# SolarPanelOptimizer.net
KiCad netlist of a schematic drawn in EAGLE
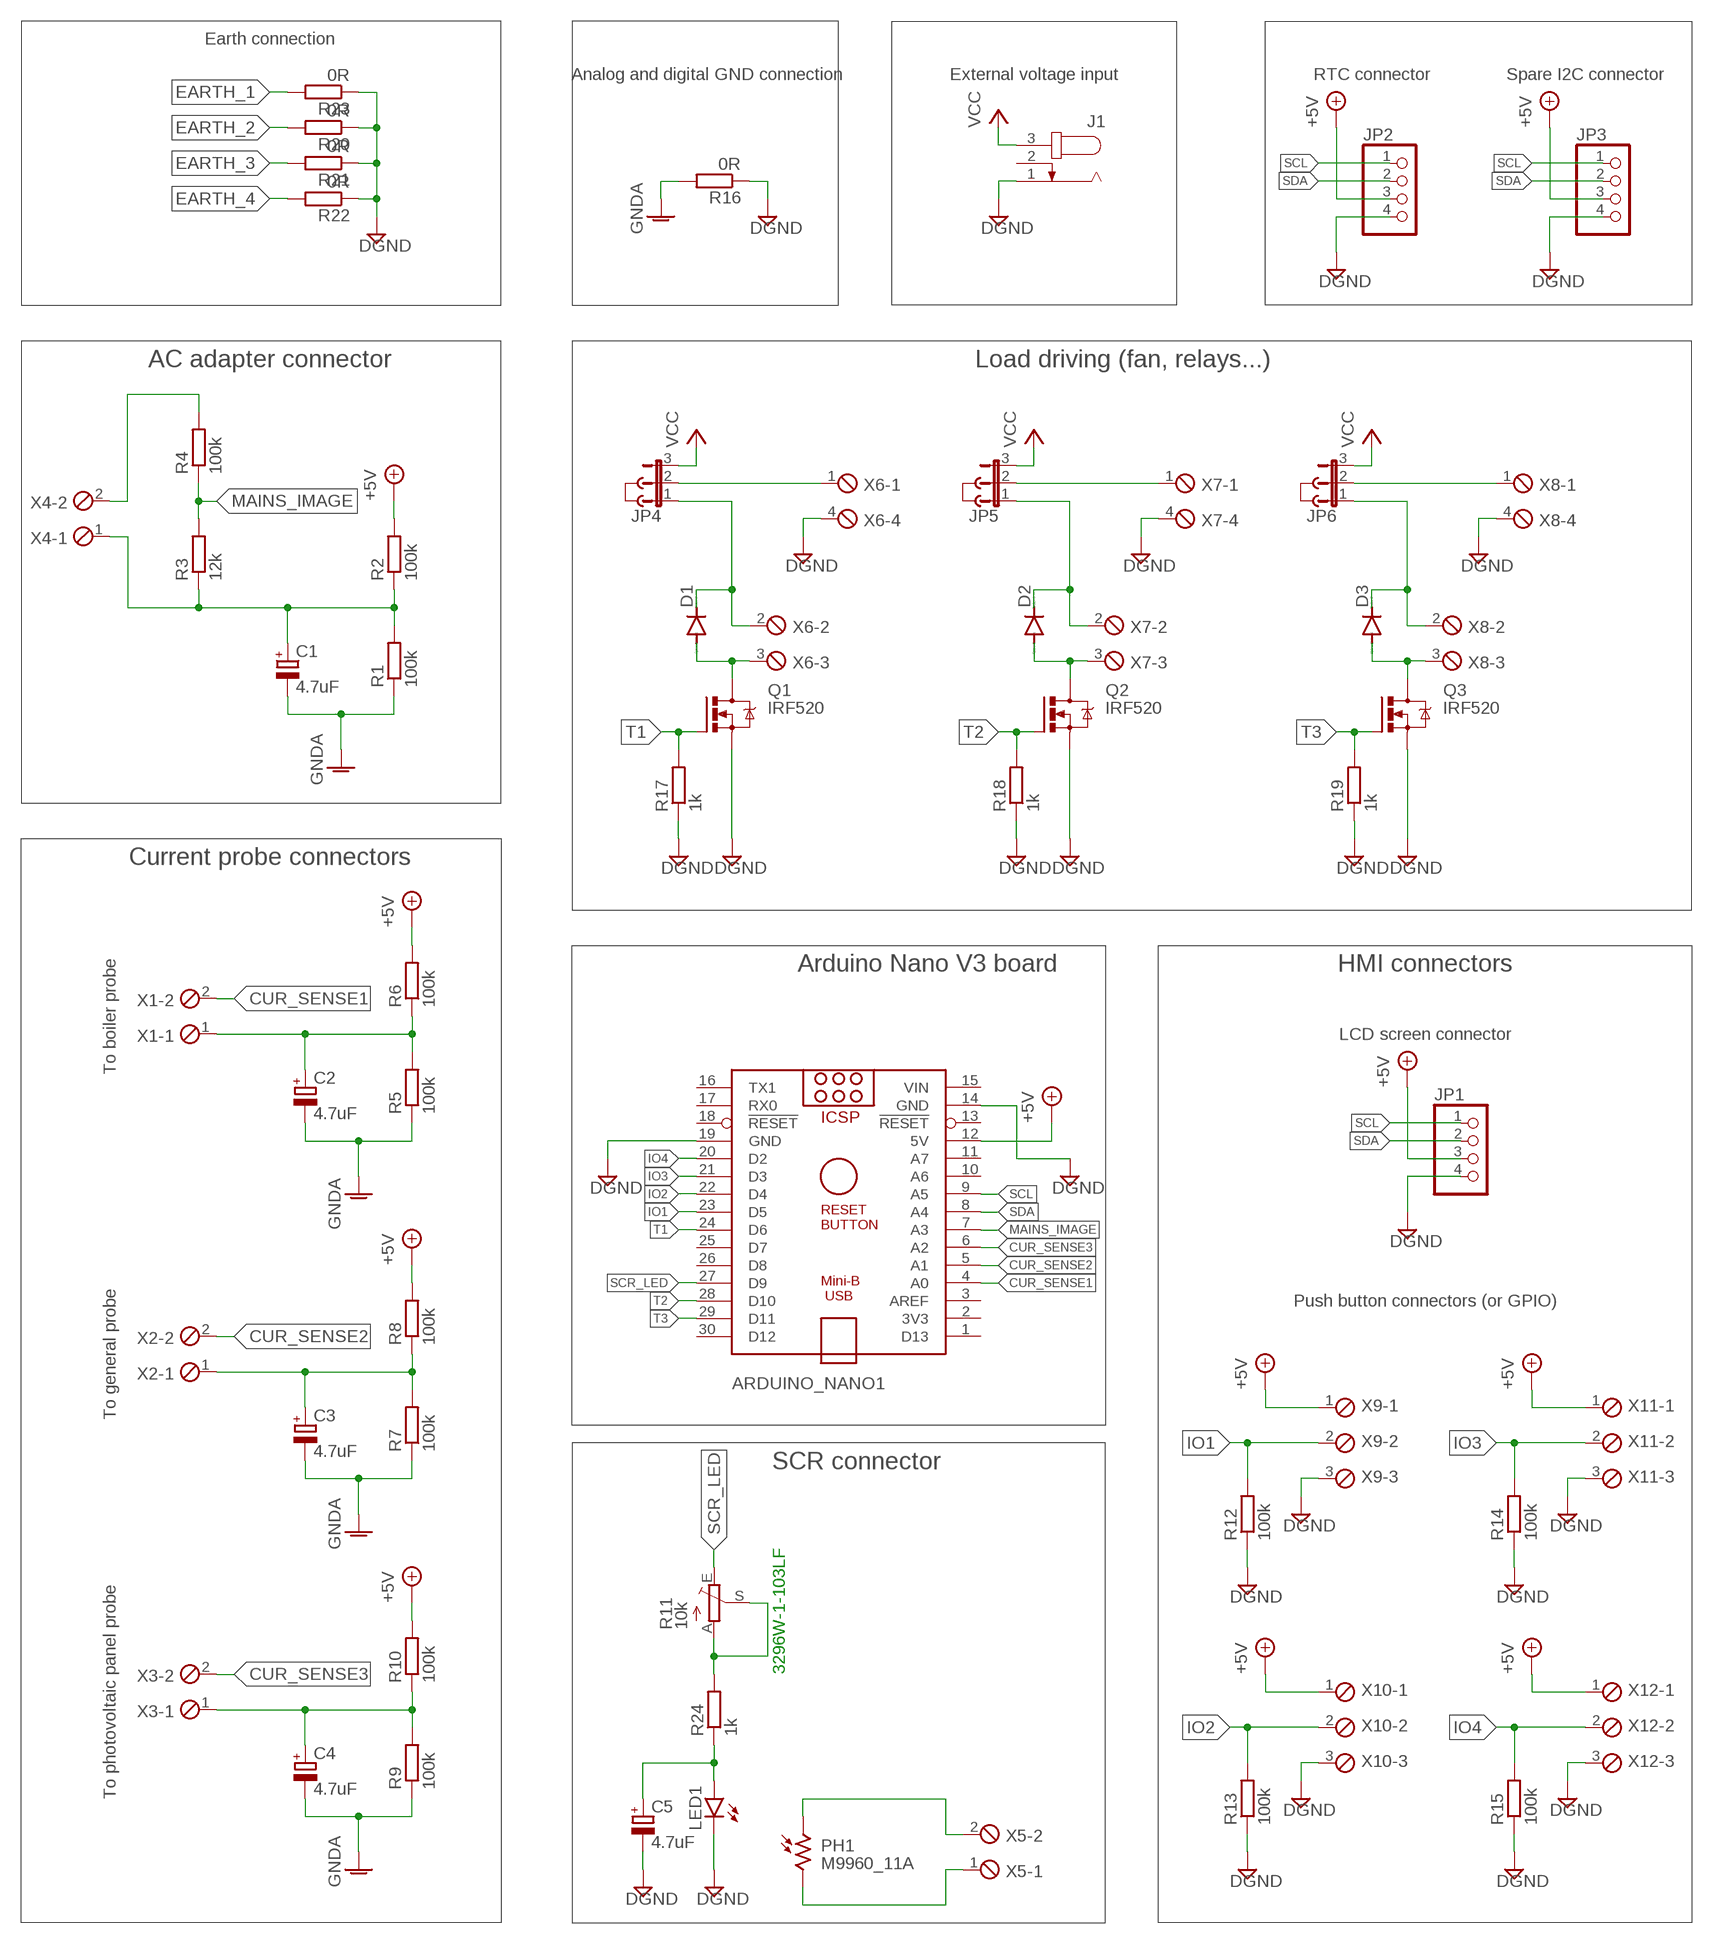
[diagram p0: schematic, sheet 1]

(export (version "E")
  (design (tool "Eeschema 10.0.6"))
  (components
    (comp (ref "ARDUINO_NANO1")
      (value "ARDUINO_NANO")
      (footprint "eagle-import:ARDUINO_NANO")
      (libsource (lib "eagle-import") (part "ARDUINO_NANO"))
    )
    (comp (ref "C1")
      (value "4.7uF")
      (footprint "eagle-import:E2-5")
      (libsource (lib "eagle-import") (part "CPOL-EUE2-5"))
    )
    (comp (ref "C2")
      (value "4.7uF")
      (footprint "eagle-import:E2-5")
      (libsource (lib "eagle-import") (part "CPOL-EUE2-5"))
    )
    (comp (ref "C3")
      (value "4.7uF")
      (footprint "eagle-import:E2-5")
      (libsource (lib "eagle-import") (part "CPOL-EUE2-5"))
    )
    (comp (ref "C4")
      (value "4.7uF")
      (footprint "eagle-import:E2-5")
      (libsource (lib "eagle-import") (part "CPOL-EUE2-5"))
    )
    (comp (ref "C5")
      (value "4.7uF")
      (footprint "eagle-import:E2-5")
      (libsource (lib "eagle-import") (part "CPOL-EUE2-5"))
    )
    (comp (ref "D1")
      (value "DIODE-D-2.5")
      (footprint "eagle-import:D-2.5")
      (libsource (lib "eagle-import") (part "DIODE-D-2.5"))
    )
    (comp (ref "D2")
      (value "DIODE-D-2.5")
      (footprint "eagle-import:D-2.5")
      (libsource (lib "eagle-import") (part "DIODE-D-2.5"))
    )
    (comp (ref "D3")
      (value "DIODE-D-2.5")
      (footprint "eagle-import:D-2.5")
      (libsource (lib "eagle-import") (part "DIODE-D-2.5"))
    )
    (comp (ref "J1")
      (value "JACK-PLUG0")
      (footprint "eagle-import:SPC4077")
      (libsource (lib "eagle-import") (part "JACK-PLUG0"))
    )
    (comp (ref "J2")
      (value "JUMPER")
      (footprint "eagle-import:JUMP")
      (libsource (lib "eagle-import") (part "JUMPER"))
    )
    (comp (ref "J3")
      (value "JUMPER")
      (footprint "eagle-import:JUMP")
      (libsource (lib "eagle-import") (part "JUMPER"))
    )
    (comp (ref "J4")
      (value "JUMPER")
      (footprint "eagle-import:JUMP")
      (libsource (lib "eagle-import") (part "JUMPER"))
    )
    (comp (ref "JP1")
      (value "PINHD-1X4")
      (footprint "eagle-import:1X04")
      (libsource (lib "eagle-import") (part "PINHD-1X4"))
    )
    (comp (ref "JP2")
      (value "PINHD-1X4")
      (footprint "eagle-import:1X04")
      (libsource (lib "eagle-import") (part "PINHD-1X4"))
    )
    (comp (ref "JP3")
      (value "PINHD-1X4")
      (footprint "eagle-import:1X04")
      (libsource (lib "eagle-import") (part "PINHD-1X4"))
    )
    (comp (ref "JP4")
      (value "JP2E")
      (footprint "eagle-import:JP2")
      (libsource (lib "eagle-import") (part "JP2E"))
    )
    (comp (ref "JP5")
      (value "JP2E")
      (footprint "eagle-import:JP2")
      (libsource (lib "eagle-import") (part "JP2E"))
    )
    (comp (ref "JP6")
      (value "JP2E")
      (footprint "eagle-import:JP2")
      (libsource (lib "eagle-import") (part "JP2E"))
    )
    (comp (ref "LED1")
      (value "LED3MM")
      (footprint "eagle-import:LED3MM")
      (libsource (lib "eagle-import") (part "LED3MM"))
    )
    (comp (ref "PH1")
      (value "M9960_11A")
      (footprint "eagle-import:M9960")
      (libsource (lib "eagle-import") (part "M9960_11A"))
    )
    (comp (ref "Q1")
      (value "IRF520")
      (footprint "eagle-import:TO220BV")
      (libsource (lib "eagle-import") (part "IRF520"))
    )
    (comp (ref "Q2")
      (value "IRF520")
      (footprint "eagle-import:TO220BV")
      (libsource (lib "eagle-import") (part "IRF520"))
    )
    (comp (ref "Q3")
      (value "IRF520")
      (footprint "eagle-import:TO220BV")
      (libsource (lib "eagle-import") (part "IRF520"))
    )
    (comp (ref "R1")
      (value "100k")
      (footprint "eagle-import:0204V")
      (libsource (lib "eagle-import") (part "R-EU_0204/2V"))
    )
    (comp (ref "R2")
      (value "100k")
      (footprint "eagle-import:0204V")
      (libsource (lib "eagle-import") (part "R-EU_0204/2V"))
    )
    (comp (ref "R3")
      (value "12k")
      (footprint "eagle-import:0204V")
      (libsource (lib "eagle-import") (part "R-EU_0204/2V"))
    )
    (comp (ref "R4")
      (value "100k")
      (footprint "eagle-import:0204V")
      (libsource (lib "eagle-import") (part "R-EU_0204/2V"))
    )
    (comp (ref "R5")
      (value "100k")
      (footprint "eagle-import:0204V")
      (libsource (lib "eagle-import") (part "R-EU_0204/2V"))
    )
    (comp (ref "R6")
      (value "100k")
      (footprint "eagle-import:0204V")
      (libsource (lib "eagle-import") (part "R-EU_0204/2V"))
    )
    (comp (ref "R7")
      (value "100k")
      (footprint "eagle-import:0204V")
      (libsource (lib "eagle-import") (part "R-EU_0204/2V"))
    )
    (comp (ref "R8")
      (value "100k")
      (footprint "eagle-import:0204V")
      (libsource (lib "eagle-import") (part "R-EU_0204/2V"))
    )
    (comp (ref "R9")
      (value "100k")
      (footprint "eagle-import:0204V")
      (libsource (lib "eagle-import") (part "R-EU_0204/2V"))
    )
    (comp (ref "R10")
      (value "100k")
      (footprint "eagle-import:0204V")
      (libsource (lib "eagle-import") (part "R-EU_0204/2V"))
    )
    (comp (ref "R11")
      (value "10k")
      (footprint "eagle-import:RJ9W")
      (libsource (lib "eagle-import") (part "TRIM_EU-RJ9W"))
    )
    (comp (ref "R12")
      (value "100k")
      (footprint "eagle-import:0204V")
      (libsource (lib "eagle-import") (part "R-EU_0204/2V"))
    )
    (comp (ref "R13")
      (value "100k")
      (footprint "eagle-import:0204V")
      (libsource (lib "eagle-import") (part "R-EU_0204/2V"))
    )
    (comp (ref "R14")
      (value "100k")
      (footprint "eagle-import:0204V")
      (libsource (lib "eagle-import") (part "R-EU_0204/2V"))
    )
    (comp (ref "R15")
      (value "100k")
      (footprint "eagle-import:0204V")
      (libsource (lib "eagle-import") (part "R-EU_0204/2V"))
    )
    (comp (ref "R16")
      (value "0R")
      (footprint "eagle-import:R0805")
      (libsource (lib "eagle-import") (part "R-EU_R0805"))
    )
    (comp (ref "R17")
      (value "1k")
      (footprint "eagle-import:0204V")
      (libsource (lib "eagle-import") (part "R-EU_0204/2V"))
    )
    (comp (ref "R18")
      (value "1k")
      (footprint "eagle-import:0204V")
      (libsource (lib "eagle-import") (part "R-EU_0204/2V"))
    )
    (comp (ref "R19")
      (value "1k")
      (footprint "eagle-import:0204V")
      (libsource (lib "eagle-import") (part "R-EU_0204/2V"))
    )
    (comp (ref "R20")
      (value "0R")
      (footprint "eagle-import:R0805")
      (libsource (lib "eagle-import") (part "R-EU_R0805"))
    )
    (comp (ref "R21")
      (value "0R")
      (footprint "eagle-import:R0805")
      (libsource (lib "eagle-import") (part "R-EU_R0805"))
    )
    (comp (ref "R22")
      (value "0R")
      (footprint "eagle-import:R0805")
      (libsource (lib "eagle-import") (part "R-EU_R0805"))
    )
    (comp (ref "R23")
      (value "0R")
      (footprint "eagle-import:R0805")
      (libsource (lib "eagle-import") (part "R-EU_R0805"))
    )
    (comp (ref "R24")
      (value "1k")
      (footprint "eagle-import:0204V")
      (libsource (lib "eagle-import") (part "R-EU_0204/2V"))
    )
    (comp (ref "X1")
      (value "MPT2-REAL")
      (footprint "eagle-import:2POL254-REAL")
      (libsource (lib "eagle-import") (part "MPT2-REAL"))
    )
    (comp (ref "X2")
      (value "MPT2-REAL")
      (footprint "eagle-import:2POL254-REAL")
      (libsource (lib "eagle-import") (part "MPT2-REAL"))
    )
    (comp (ref "X3")
      (value "MPT2-REAL")
      (footprint "eagle-import:2POL254-REAL")
      (libsource (lib "eagle-import") (part "MPT2-REAL"))
    )
    (comp (ref "X4")
      (value "MPT2-REAL")
      (footprint "eagle-import:2POL254-REAL")
      (libsource (lib "eagle-import") (part "MPT2-REAL"))
    )
    (comp (ref "X5")
      (value "MPT2-REAL")
      (footprint "eagle-import:2POL254-REAL")
      (libsource (lib "eagle-import") (part "MPT2-REAL"))
    )
    (comp (ref "X6")
      (value "MPT4-REAL")
      (footprint "eagle-import:4POL254-REAL")
      (libsource (lib "eagle-import") (part "MPT4-REAL"))
    )
    (comp (ref "X7")
      (value "MPT4-REAL")
      (footprint "eagle-import:4POL254-REAL")
      (libsource (lib "eagle-import") (part "MPT4-REAL"))
    )
    (comp (ref "X8")
      (value "MPT4-REAL")
      (footprint "eagle-import:4POL254-REAL")
      (libsource (lib "eagle-import") (part "MPT4-REAL"))
    )
    (comp (ref "X9")
      (value "MPT3-REAL")
      (footprint "eagle-import:3POL254-REAL")
      (libsource (lib "eagle-import") (part "MPT3-REAL"))
    )
    (comp (ref "X10")
      (value "MPT3-REAL")
      (footprint "eagle-import:3POL254-REAL")
      (libsource (lib "eagle-import") (part "MPT3-REAL"))
    )
    (comp (ref "X11")
      (value "MPT3-REAL")
      (footprint "eagle-import:3POL254-REAL")
      (libsource (lib "eagle-import") (part "MPT3-REAL"))
    )
    (comp (ref "X12")
      (value "MPT3-REAL")
      (footprint "eagle-import:3POL254-REAL")
      (libsource (lib "eagle-import") (part "MPT3-REAL"))
    )
  )
  (nets
    (net (code "1") (name "+5V") (class "Default")
      (node (ref "ARDUINO_NANO1") (pin "12") (pinfunction "5V_12") (pintype "power_in"))
      (node (ref "JP1") (pin "3") (pinfunction "3_3") (pintype "passive"))
      (node (ref "JP2") (pin "3") (pinfunction "3_3") (pintype "passive"))
      (node (ref "JP3") (pin "3") (pinfunction "3_3") (pintype "passive"))
      (node (ref "R10") (pin "2") (pinfunction "2_2") (pintype "passive"))
      (node (ref "R2") (pin "2") (pinfunction "2_2") (pintype "passive"))
      (node (ref "R6") (pin "2") (pinfunction "2_2") (pintype "passive"))
      (node (ref "R8") (pin "2") (pinfunction "2_2") (pintype "passive"))
      (node (ref "X10") (pin "1") (pinfunction "1_1") (pintype "passive"))
      (node (ref "X11") (pin "1") (pinfunction "1_1") (pintype "passive"))
      (node (ref "X12") (pin "1") (pinfunction "1_1") (pintype "passive"))
      (node (ref "X9") (pin "1") (pinfunction "1_1") (pintype "passive"))
    )
    (net (code "2") (name "/VIN") (class "Default")
      (node (ref "ARDUINO_NANO1") (pin "15") (pinfunction "VIN_15") (pintype "power_in"))
    )
    (net (code "3") (name "CUR_SENSE1") (class "Default")
      (node (ref "ARDUINO_NANO1") (pin "4") (pinfunction "A0_4") (pintype "bidirectional"))
      (node (ref "X1") (pin "2") (pinfunction "1_2") (pintype "passive"))
    )
    (net (code "4") (name "CUR_SENSE2") (class "Default")
      (node (ref "ARDUINO_NANO1") (pin "5") (pinfunction "A1_5") (pintype "bidirectional"))
      (node (ref "X2") (pin "2") (pinfunction "1_2") (pintype "passive"))
    )
    (net (code "5") (name "CUR_SENSE3") (class "Default")
      (node (ref "ARDUINO_NANO1") (pin "6") (pinfunction "A2_6") (pintype "bidirectional"))
      (node (ref "X3") (pin "2") (pinfunction "1_2") (pintype "passive"))
    )
    (net (code "6") (name "DGND") (class "Default")
      (node (ref "ARDUINO_NANO1") (pin "14") (pinfunction "GND_14") (pintype "power_in"))
      (node (ref "ARDUINO_NANO1") (pin "19") (pinfunction "GND_19") (pintype "power_in"))
      (node (ref "C5") (pin "-") (pinfunction "-_-") (pintype "passive"))
      (node (ref "J1") (pin "1") (pinfunction "1_1") (pintype "passive"))
      (node (ref "JP1") (pin "4") (pinfunction "4_4") (pintype "passive"))
      (node (ref "JP2") (pin "4") (pinfunction "4_4") (pintype "passive"))
      (node (ref "JP3") (pin "4") (pinfunction "4_4") (pintype "passive"))
      (node (ref "LED1") (pin "K") (pinfunction "C_K") (pintype "passive"))
      (node (ref "Q1") (pin "S") (pinfunction "S_S") (pintype "passive"))
      (node (ref "Q2") (pin "S") (pinfunction "S_S") (pintype "passive"))
      (node (ref "Q3") (pin "S") (pinfunction "S_S") (pintype "passive"))
      (node (ref "R12") (pin "1") (pinfunction "1_1") (pintype "passive"))
      (node (ref "R13") (pin "1") (pinfunction "1_1") (pintype "passive"))
      (node (ref "R14") (pin "1") (pinfunction "1_1") (pintype "passive"))
      (node (ref "R15") (pin "1") (pinfunction "1_1") (pintype "passive"))
      (node (ref "R16") (pin "1") (pinfunction "1_1") (pintype "passive"))
      (node (ref "R17") (pin "1") (pinfunction "1_1") (pintype "passive"))
      (node (ref "R18") (pin "1") (pinfunction "1_1") (pintype "passive"))
      (node (ref "R19") (pin "1") (pinfunction "1_1") (pintype "passive"))
      (node (ref "R20") (pin "1") (pinfunction "1_1") (pintype "passive"))
      (node (ref "R21") (pin "1") (pinfunction "1_1") (pintype "passive"))
      (node (ref "R22") (pin "1") (pinfunction "1_1") (pintype "passive"))
      (node (ref "R23") (pin "1") (pinfunction "1_1") (pintype "passive"))
      (node (ref "X10") (pin "3") (pinfunction "1_3") (pintype "passive"))
      (node (ref "X11") (pin "3") (pinfunction "1_3") (pintype "passive"))
      (node (ref "X12") (pin "3") (pinfunction "1_3") (pintype "passive"))
      (node (ref "X6") (pin "4") (pinfunction "1_4") (pintype "passive"))
      (node (ref "X7") (pin "4") (pinfunction "1_4") (pintype "passive"))
      (node (ref "X8") (pin "4") (pinfunction "1_4") (pintype "passive"))
      (node (ref "X9") (pin "3") (pinfunction "1_3") (pintype "passive"))
    )
    (net (code "7") (name "EARTH_1") (class "Default")
      (node (ref "R23") (pin "2") (pinfunction "2_2") (pintype "passive"))
    )
    (net (code "8") (name "EARTH_2") (class "Default")
      (node (ref "R20") (pin "2") (pinfunction "2_2") (pintype "passive"))
    )
    (net (code "9") (name "EARTH_3") (class "Default")
      (node (ref "R21") (pin "2") (pinfunction "2_2") (pintype "passive"))
    )
    (net (code "10") (name "EARTH_4") (class "Default")
      (node (ref "R22") (pin "2") (pinfunction "2_2") (pintype "passive"))
    )
    (net (code "11") (name "GNDA") (class "Default")
      (node (ref "C1") (pin "-") (pinfunction "-_-") (pintype "passive"))
      (node (ref "C2") (pin "-") (pinfunction "-_-") (pintype "passive"))
      (node (ref "C3") (pin "-") (pinfunction "-_-") (pintype "passive"))
      (node (ref "C4") (pin "-") (pinfunction "-_-") (pintype "passive"))
      (node (ref "R1") (pin "1") (pinfunction "1_1") (pintype "passive"))
      (node (ref "R16") (pin "2") (pinfunction "2_2") (pintype "passive"))
      (node (ref "R5") (pin "1") (pinfunction "1_1") (pintype "passive"))
      (node (ref "R7") (pin "1") (pinfunction "1_1") (pintype "passive"))
      (node (ref "R9") (pin "1") (pinfunction "1_1") (pintype "passive"))
    )
    (net (code "12") (name "IO1") (class "Default")
      (node (ref "ARDUINO_NANO1") (pin "23") (pinfunction "D5_23") (pintype "bidirectional"))
      (node (ref "R12") (pin "2") (pinfunction "2_2") (pintype "passive"))
      (node (ref "X9") (pin "2") (pinfunction "1_2") (pintype "passive"))
    )
    (net (code "13") (name "IO2") (class "Default")
      (node (ref "ARDUINO_NANO1") (pin "22") (pinfunction "D4_22") (pintype "bidirectional"))
      (node (ref "R13") (pin "2") (pinfunction "2_2") (pintype "passive"))
      (node (ref "X10") (pin "2") (pinfunction "1_2") (pintype "passive"))
    )
    (net (code "14") (name "IO3") (class "Default")
      (node (ref "ARDUINO_NANO1") (pin "21") (pinfunction "D3_21") (pintype "bidirectional"))
      (node (ref "R14") (pin "2") (pinfunction "2_2") (pintype "passive"))
      (node (ref "X11") (pin "2") (pinfunction "1_2") (pintype "passive"))
    )
    (net (code "15") (name "IO4") (class "Default")
      (node (ref "ARDUINO_NANO1") (pin "20") (pinfunction "D2_20") (pintype "bidirectional"))
      (node (ref "R15") (pin "2") (pinfunction "2_2") (pintype "passive"))
      (node (ref "X12") (pin "2") (pinfunction "1_2") (pintype "passive"))
    )
    (net (code "16") (name "MAINS_IMAGE") (class "Default")
      (node (ref "ARDUINO_NANO1") (pin "7") (pinfunction "A3_7") (pintype "bidirectional"))
      (node (ref "R3") (pin "2") (pinfunction "2_2") (pintype "passive"))
      (node (ref "R4") (pin "1") (pinfunction "1_1") (pintype "passive"))
    )
    (net (code "17") (name "Net-(C1-Pad+)") (class "Default")
      (node (ref "C1") (pin "+") (pinfunction "+_+") (pintype "passive"))
      (node (ref "R1") (pin "2") (pinfunction "2_2") (pintype "passive"))
      (node (ref "R2") (pin "1") (pinfunction "1_1") (pintype "passive"))
      (node (ref "R3") (pin "1") (pinfunction "1_1") (pintype "passive"))
      (node (ref "X4") (pin "1") (pinfunction "1_1") (pintype "passive"))
    )
    (net (code "18") (name "Net-(C2-Pad+)") (class "Default")
      (node (ref "C2") (pin "+") (pinfunction "+_+") (pintype "passive"))
      (node (ref "R5") (pin "2") (pinfunction "2_2") (pintype "passive"))
      (node (ref "R6") (pin "1") (pinfunction "1_1") (pintype "passive"))
      (node (ref "X1") (pin "1") (pinfunction "1_1") (pintype "passive"))
    )
    (net (code "19") (name "Net-(C3-Pad+)") (class "Default")
      (node (ref "C3") (pin "+") (pinfunction "+_+") (pintype "passive"))
      (node (ref "R7") (pin "2") (pinfunction "2_2") (pintype "passive"))
      (node (ref "R8") (pin "1") (pinfunction "1_1") (pintype "passive"))
      (node (ref "X2") (pin "1") (pinfunction "1_1") (pintype "passive"))
    )
    (net (code "20") (name "Net-(C4-Pad+)") (class "Default")
      (node (ref "C4") (pin "+") (pinfunction "+_+") (pintype "passive"))
      (node (ref "R10") (pin "1") (pinfunction "1_1") (pintype "passive"))
      (node (ref "R9") (pin "2") (pinfunction "2_2") (pintype "passive"))
      (node (ref "X3") (pin "1") (pinfunction "1_1") (pintype "passive"))
    )
    (net (code "21") (name "Net-(C5-Pad+)") (class "Default")
      (node (ref "C5") (pin "+") (pinfunction "+_+") (pintype "passive"))
      (node (ref "LED1") (pin "A") (pinfunction "A_A") (pintype "passive"))
      (node (ref "R24") (pin "1") (pinfunction "1_1") (pintype "passive"))
    )
    (net (code "22") (name "Net-(JP4-Pad2)") (class "Default")
      (node (ref "JP4") (pin "2") (pinfunction "2_2") (pintype "passive"))
      (node (ref "X6") (pin "1") (pinfunction "1_1") (pintype "passive"))
    )
    (net (code "23") (name "Net-(JP5-Pad2)") (class "Default")
      (node (ref "JP5") (pin "2") (pinfunction "2_2") (pintype "passive"))
      (node (ref "X7") (pin "1") (pinfunction "1_1") (pintype "passive"))
    )
    (net (code "24") (name "Net-(JP6-Pad2)") (class "Default")
      (node (ref "JP6") (pin "2") (pinfunction "2_2") (pintype "passive"))
      (node (ref "X8") (pin "1") (pinfunction "1_1") (pintype "passive"))
    )
    (net (code "25") (name "Net-(PH1-Pad2)") (class "Default")
      (node (ref "PH1") (pin "2") (pinfunction "2_2") (pintype "passive"))
      (node (ref "X5") (pin "1") (pinfunction "1_1") (pintype "passive"))
    )
    (net (code "26") (name "Net-(R11-PadA)") (class "Default")
      (node (ref "R11") (pin "A") (pinfunction "A_A") (pintype "passive"))
      (node (ref "R11") (pin "S") (pinfunction "S_S") (pintype "passive"))
      (node (ref "R24") (pin "2") (pinfunction "2_2") (pintype "passive"))
    )
    (net (code "27") (name "Net-(X4B-1)") (class "Default")
      (node (ref "R4") (pin "2") (pinfunction "2_2") (pintype "passive"))
      (node (ref "X4") (pin "2") (pinfunction "1_2") (pintype "passive"))
    )
    (net (code "28") (name "Net-(X5B-1)") (class "Default")
      (node (ref "PH1") (pin "1") (pinfunction "1_1") (pintype "passive"))
      (node (ref "X5") (pin "2") (pinfunction "1_2") (pintype "passive"))
    )
    (net (code "29") (name "Net-(X6B-1)") (class "Default")
      (node (ref "D1") (pin "C") (pinfunction "C_C") (pintype "passive"))
      (node (ref "JP4") (pin "1") (pinfunction "1_1") (pintype "passive"))
      (node (ref "X6") (pin "2") (pinfunction "1_2") (pintype "passive"))
    )
    (net (code "30") (name "Net-(X6C-1)") (class "Default")
      (node (ref "D1") (pin "A") (pinfunction "A_A") (pintype "passive"))
      (node (ref "Q1") (pin "D") (pinfunction "D_D") (pintype "passive"))
      (node (ref "X6") (pin "3") (pinfunction "1_3") (pintype "passive"))
    )
    (net (code "31") (name "Net-(X7B-1)") (class "Default")
      (node (ref "D2") (pin "C") (pinfunction "C_C") (pintype "passive"))
      (node (ref "JP5") (pin "1") (pinfunction "1_1") (pintype "passive"))
      (node (ref "X7") (pin "2") (pinfunction "1_2") (pintype "passive"))
    )
    (net (code "32") (name "Net-(X7C-1)") (class "Default")
      (node (ref "D2") (pin "A") (pinfunction "A_A") (pintype "passive"))
      (node (ref "Q2") (pin "D") (pinfunction "D_D") (pintype "passive"))
      (node (ref "X7") (pin "3") (pinfunction "1_3") (pintype "passive"))
    )
    (net (code "33") (name "Net-(X8B-1)") (class "Default")
      (node (ref "D3") (pin "C") (pinfunction "C_C") (pintype "passive"))
      (node (ref "JP6") (pin "1") (pinfunction "1_1") (pintype "passive"))
      (node (ref "X8") (pin "2") (pinfunction "1_2") (pintype "passive"))
    )
    (net (code "34") (name "Net-(X8C-1)") (class "Default")
      (node (ref "D3") (pin "A") (pinfunction "A_A") (pintype "passive"))
      (node (ref "Q3") (pin "D") (pinfunction "D_D") (pintype "passive"))
      (node (ref "X8") (pin "3") (pinfunction "1_3") (pintype "passive"))
    )
    (net (code "35") (name "SCL") (class "Default")
      (node (ref "ARDUINO_NANO1") (pin "9") (pinfunction "A5_9") (pintype "bidirectional"))
      (node (ref "JP1") (pin "1") (pinfunction "1_1") (pintype "passive"))
      (node (ref "JP2") (pin "1") (pinfunction "1_1") (pintype "passive"))
      (node (ref "JP3") (pin "1") (pinfunction "1_1") (pintype "passive"))
    )
    (net (code "36") (name "SCR_LED") (class "Default")
      (node (ref "ARDUINO_NANO1") (pin "27") (pinfunction "D9_27") (pintype "bidirectional"))
      (node (ref "R11") (pin "E") (pinfunction "E_E") (pintype "passive"))
    )
    (net (code "37") (name "SDA") (class "Default")
      (node (ref "ARDUINO_NANO1") (pin "8") (pinfunction "A4_8") (pintype "bidirectional"))
      (node (ref "JP1") (pin "2") (pinfunction "2_2") (pintype "passive"))
      (node (ref "JP2") (pin "2") (pinfunction "2_2") (pintype "passive"))
      (node (ref "JP3") (pin "2") (pinfunction "2_2") (pintype "passive"))
    )
    (net (code "38") (name "T1") (class "Default")
      (node (ref "ARDUINO_NANO1") (pin "24") (pinfunction "D6_24") (pintype "bidirectional"))
      (node (ref "Q1") (pin "G") (pinfunction "G_G") (pintype "passive"))
      (node (ref "R17") (pin "2") (pinfunction "2_2") (pintype "passive"))
    )
    (net (code "39") (name "T2") (class "Default")
      (node (ref "ARDUINO_NANO1") (pin "28") (pinfunction "D10_28") (pintype "bidirectional"))
      (node (ref "Q2") (pin "G") (pinfunction "G_G") (pintype "passive"))
      (node (ref "R18") (pin "2") (pinfunction "2_2") (pintype "passive"))
    )
    (net (code "40") (name "T3") (class "Default")
      (node (ref "ARDUINO_NANO1") (pin "29") (pinfunction "D11_29") (pintype "bidirectional"))
      (node (ref "Q3") (pin "G") (pinfunction "G_G") (pintype "passive"))
      (node (ref "R19") (pin "2") (pinfunction "2_2") (pintype "passive"))
    )
    (net (code "41") (name "VCC") (class "Default")
      (node (ref "J1") (pin "3") (pinfunction "3_3") (pintype "passive"))
      (node (ref "JP4") (pin "3") (pinfunction "3_3") (pintype "passive"))
      (node (ref "JP5") (pin "3") (pinfunction "3_3") (pintype "passive"))
      (node (ref "JP6") (pin "3") (pinfunction "3_3") (pintype "passive"))
    )
    (net (code "42") (name "unconnected-(ARDUINO_NANO1-3V3-Pad2)") (class "Default")
      (node (ref "ARDUINO_NANO1") (pin "2") (pinfunction "3V3_2") (pintype "output"))
    )
    (net (code "43") (name "unconnected-(ARDUINO_NANO1-A6-Pad10)") (class "Default")
      (node (ref "ARDUINO_NANO1") (pin "10") (pinfunction "A6_10") (pintype "bidirectional"))
    )
    (net (code "44") (name "unconnected-(ARDUINO_NANO1-A7-Pad11)") (class "Default")
      (node (ref "ARDUINO_NANO1") (pin "11") (pinfunction "A7_11") (pintype "bidirectional"))
    )
    (net (code "45") (name "unconnected-(ARDUINO_NANO1-AREF-Pad3)") (class "Default")
      (node (ref "ARDUINO_NANO1") (pin "3") (pinfunction "AREF_3") (pintype "input"))
    )
    (net (code "46") (name "unconnected-(ARDUINO_NANO1-D7-Pad25)") (class "Default")
      (node (ref "ARDUINO_NANO1") (pin "25") (pinfunction "D7_25") (pintype "bidirectional"))
    )
    (net (code "47") (name "unconnected-(ARDUINO_NANO1-D8-Pad26)") (class "Default")
      (node (ref "ARDUINO_NANO1") (pin "26") (pinfunction "D8_26") (pintype "bidirectional"))
    )
    (net (code "48") (name "unconnected-(ARDUINO_NANO1-D12-Pad30)") (class "Default")
      (node (ref "ARDUINO_NANO1") (pin "30") (pinfunction "D12_30") (pintype "bidirectional"))
    )
    (net (code "49") (name "unconnected-(ARDUINO_NANO1-D13-Pad1)") (class "Default")
      (node (ref "ARDUINO_NANO1") (pin "1") (pinfunction "D13_1") (pintype "bidirectional"))
    )
    (net (code "50") (name "unconnected-(ARDUINO_NANO1-RX0-Pad17)") (class "Default")
      (node (ref "ARDUINO_NANO1") (pin "17") (pinfunction "RX0_17") (pintype "bidirectional"))
    )
    (net (code "51") (name "unconnected-(ARDUINO_NANO1-TX1-Pad16)") (class "Default")
      (node (ref "ARDUINO_NANO1") (pin "16") (pinfunction "TX1_16") (pintype "bidirectional"))
    )
    (net (code "52") (name "unconnected-(ARDUINO_NANO1-~{RESET}-Pad13)") (class "Default")
      (node (ref "ARDUINO_NANO1") (pin "13") (pinfunction "~{RESET}_13") (pintype "input"))
    )
    (net (code "53") (name "unconnected-(ARDUINO_NANO1-~{RESET}-Pad18)") (class "Default")
      (node (ref "ARDUINO_NANO1") (pin "18") (pinfunction "~{RESET}_18") (pintype "input"))
    )
    (net (code "54") (name "unconnected-(J1-Pad2)") (class "Default")
      (node (ref "J1") (pin "2") (pinfunction "2_2") (pintype "passive"))
    )
  )
)
